# SCH_W-F-FC-HX2X_BASE.net
KiCad netlist of a schematic drawn in Altium Designer
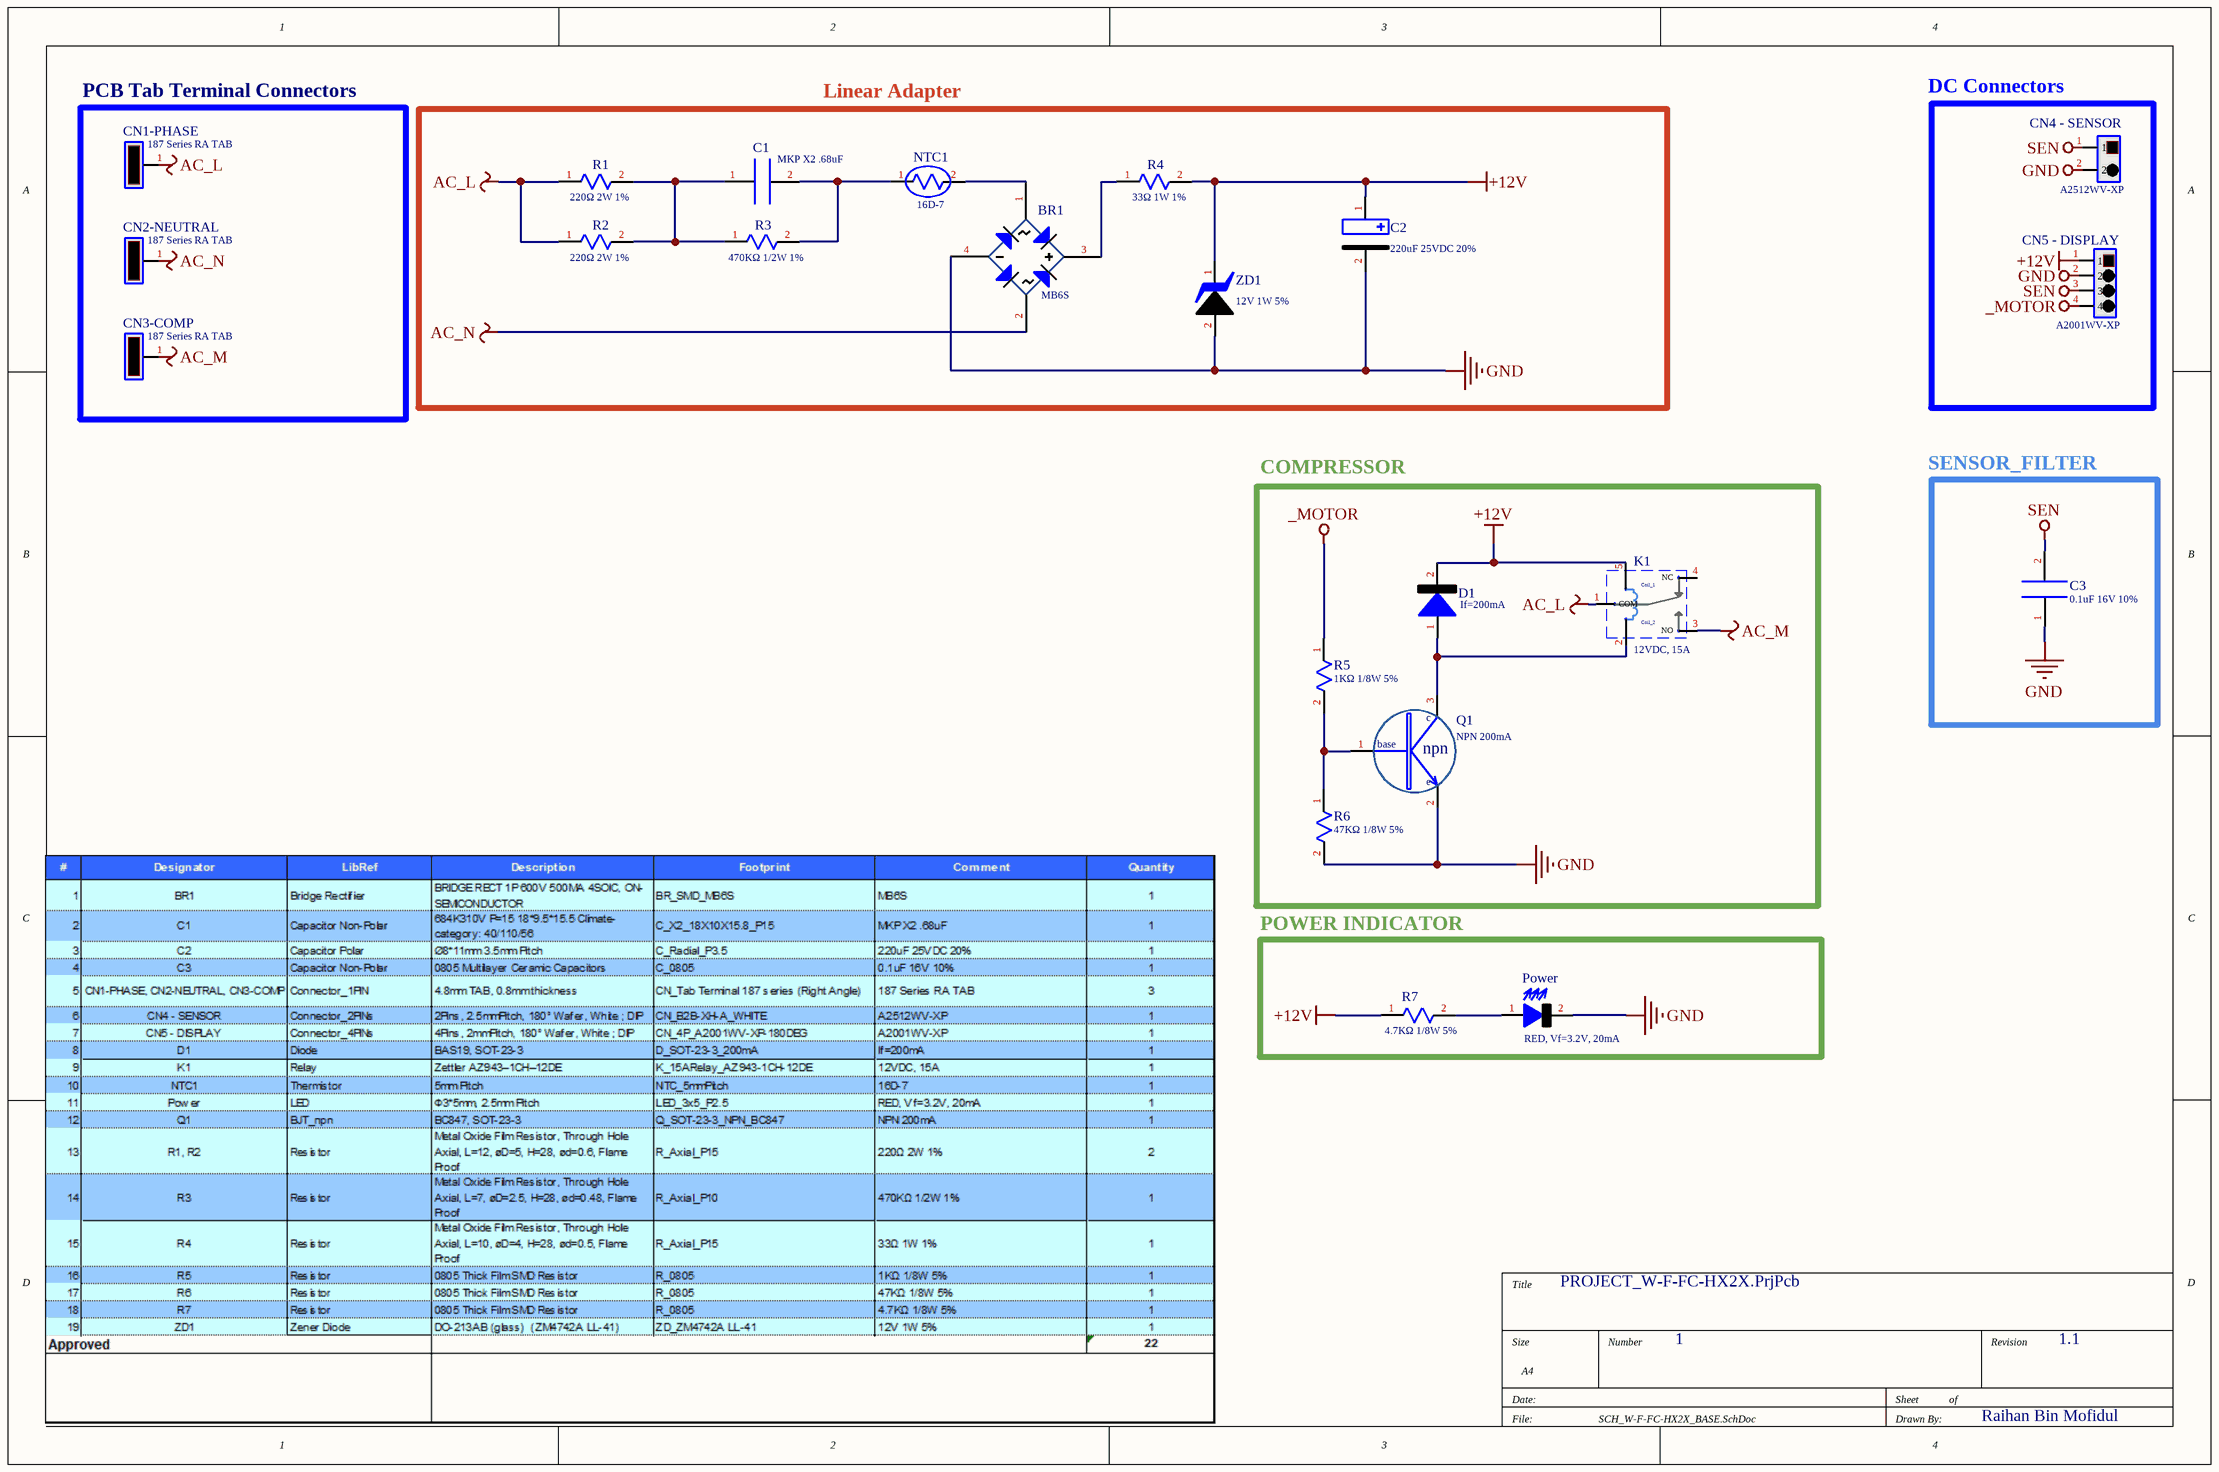
[diagram p0: SCH_W-F-FC-HX2X_BASE.SchDoc]

(export (version "E")
  (design (tool "Eeschema 10.0.6"))
  (components
    (comp (ref "BR1")
      (value "MB6S")
      (footprint "BR_SMD_MB6S")
      (description "BRIDGE RECT 1P 600V 500MA 4SOIC, ON-SEMICONDUCTOR")
      (libsource (lib "RBM_SCH-LIB_02-SEP-19") (part "Bridge Rectifier"))
    )
    (comp (ref "C1")
      (value "MKP X2 .68uF")
      (footprint "C_X2_18X10X15.8_P15")
      (description "684K310V P=15 18*9.5*15.5 Climate-category: 40/110/56")
      (libsource (lib "RBM_SCH-LIB_02-SEP-19") (part "Capacitor Non-Polar"))
    )
    (comp (ref "C2")
      (value "220uF 25VDC 20%")
      (footprint "C_Radial_P3.5")
      (description "Ø8*11mm 3.5mm Pitch")
      (libsource (lib "RBM_SCH-LIB_02-SEP-19") (part "Capacitor Polar"))
    )
    (comp (ref "C3")
      (value "0.1uF 16V 10%")
      (footprint "C_0805")
      (description "0805 Multilayer Ceramic Capacitors")
      (libsource (lib "RBM_SCH-Lib_16-Apr-19") (part "Capacitor Non-Polar"))
    )
    (comp (ref "CN1-PHASE")
      (value "187 Series RA TAB")
      (footprint "CN_Tab Terminal 187 series (Right Angle)")
      (description "4.8mm TAB, 0.8mm thickness")
      (libsource (lib "RBM_SCH-LIB_02-SEP-19") (part "Connector_1PIN"))
    )
    (comp (ref "CN2-NEUTRAL")
      (value "187 Series RA TAB")
      (footprint "CN_Tab Terminal 187 series (Right Angle)")
      (description "4.8mm TAB, 0.8mm thickness")
      (libsource (lib "RBM_SCH-LIB_02-SEP-19") (part "Connector_1PIN"))
    )
    (comp (ref "CN3-COMP")
      (value "187 Series RA TAB")
      (footprint "CN_Tab Terminal 187 series (Right Angle)")
      (description "4.8mm TAB, 0.8mm thickness")
      (libsource (lib "RBM_SCH-LIB_02-SEP-19") (part "Connector_1PIN"))
    )
    (comp (ref "CN4 - SENSOR")
      (value "A2512WV-XP")
      (footprint "CN_B2B-XH-A_WHITE")
      (description "2Pins, 2.5mmPitch, 180° Wafer, White ; DIP")
      (libsource (lib "RBM_SCH-Lib_16-Apr-19") (part "Connector_2PINs"))
    )
    (comp (ref "CN5 - DISPLAY")
      (value "A2001WV-XP")
      (footprint "CN_4P_A2001WV-XP-180DEG")
      (description "4Pins, 2mmPitch, 180° Wafer, White ; DIP")
      (libsource (lib "RBM_SCH-LIB_02-SEP-19") (part "Connector_4PINs"))
    )
    (comp (ref "D1")
      (value "If=200mA")
      (footprint "D_SOT-23-3_200mA")
      (description "BAS19, SOT-23-3")
      (libsource (lib "RBM_SCH-LIB_02-SEP-19") (part "Diode"))
    )
    (comp (ref "K1")
      (value "12VDC, 15A")
      (footprint "K_15ARelay_AZ943-1CH-12DE")
      (description "Zettler AZ943–1CH–12DE")
      (libsource (lib "RBM_SCH-Lib_16-Apr-19") (part "Relay"))
    )
    (comp (ref "NTC1")
      (value "16D-7")
      (footprint "NTC_5mmPitch")
      (description "5mm Pitch")
      (libsource (lib "RBM_SCH-LIB_02-SEP-19") (part "Thermistor"))
    )
    (comp (ref "Power")
      (value "RED, Vf=3.2V, 20mA")
      (footprint "LED_3x5_P2.5")
      (description "Φ3*5mm, 2.5mm Pitch")
      (libsource (lib "RBM_SCH-LIB_02-SEP-19") (part "LED"))
    )
    (comp (ref "Q1")
      (value "NPN 200mA")
      (footprint "Q_SOT-23-3_NPN_BC847")
      (description "BC847, SOT-23-3")
      (libsource (lib "RBM_SCH-Lib_16-Apr-19") (part "BJT_npn"))
    )
    (comp (ref "R1")
      (value "220Ω 2W 1%")
      (footprint "R_Axial_P15")
      (description "Metal Oxide Film Resistor, Through Hole Axial, L=12, øD=5, H=28, ød=0.6, Flame Proof")
      (libsource (lib "RBM_SCH-LIB_02-SEP-19") (part "Resistor"))
    )
    (comp (ref "R2")
      (value "220Ω 2W 1%")
      (footprint "R_Axial_P15")
      (description "Metal Oxide Film Resistor, Through Hole Axial, L=12, øD=5, H=28, ød=0.6, Flame Proof")
      (libsource (lib "RBM_SCH-LIB_02-SEP-19") (part "Resistor"))
    )
    (comp (ref "R3")
      (value "470KΩ 1/2W 1%")
      (footprint "R_Axial_P10")
      (description "Metal Oxide Film Resistor, Through Hole Axial, L=7, øD=2.5, H=28, ød=0.48, Flame Proof")
      (libsource (lib "RBM_SCH-LIB_02-SEP-19") (part "Resistor"))
    )
    (comp (ref "R4")
      (value "33Ω 1W 1%")
      (footprint "R_Axial_P15")
      (description "Metal Oxide Film Resistor, Through Hole Axial, L=10, øD=4, H=28, ød=0.5, Flame Proof")
      (libsource (lib "RBM_SCH-LIB_02-SEP-19") (part "Resistor"))
    )
    (comp (ref "R5")
      (value "1KΩ 1/8W 5%")
      (footprint "R_0805")
      (description "0805 Thick Film SMD Resistor")
      (libsource (lib "RBM_SCH-Lib_16-Apr-19") (part "Resistor"))
    )
    (comp (ref "R6")
      (value "47KΩ 1/8W 5%")
      (footprint "R_0805")
      (description "0805 Thick Film SMD Resistor")
      (libsource (lib "RBM_SCH-Lib_16-Apr-19") (part "Resistor"))
    )
    (comp (ref "R7")
      (value "4.7KΩ 1/8W 5%")
      (footprint "R_0805")
      (description "0805 Thick Film SMD Resistor")
      (libsource (lib "RBM_SCH-Lib_16-Apr-19") (part "Resistor"))
    )
    (comp (ref "ZD1")
      (value "12V 1W 5%")
      (footprint "ZD_ZM4742A LL-41")
      (description "DO-213AB (glass)  (ZM4742A LL-41)")
      (libsource (lib "RBM_SCH-LIB_02-SEP-19") (part "Zener Diode"))
    )
  )
  (nets
    (net (code "1") (name "+12V") (class "Default")
      (node (ref "C2") (pin "1") (pinfunction "vdd_1") (pintype "passive"))
      (node (ref "CN5 - DISPLAY") (pin "1") (pinfunction "1_1") (pintype "passive"))
      (node (ref "D1") (pin "2") (pinfunction "vss_2") (pintype "passive"))
      (node (ref "K1") (pin "5") (pinfunction "COIL1_5") (pintype "passive"))
      (node (ref "R4") (pin "2") (pinfunction "2_2") (pintype "passive"))
      (node (ref "R7") (pin "1") (pinfunction "1_1") (pintype "passive"))
      (node (ref "ZD1") (pin "1") (pinfunction "VCC_1") (pintype "passive"))
    )
    (net (code "2") (name "AC_L") (class "Default")
      (node (ref "CN1-PHASE") (pin "1") (pinfunction "1_1") (pintype "passive"))
      (node (ref "K1") (pin "1") (pinfunction "COM_1") (pintype "passive"))
      (node (ref "R1") (pin "1") (pinfunction "1_1") (pintype "passive"))
      (node (ref "R2") (pin "1") (pinfunction "1_1") (pintype "passive"))
    )
    (net (code "3") (name "AC_M") (class "Default")
      (node (ref "CN3-COMP") (pin "1") (pinfunction "1_1") (pintype "passive"))
      (node (ref "K1") (pin "3") (pinfunction "NO_3") (pintype "passive"))
    )
    (net (code "4") (name "AC_N") (class "Default")
      (node (ref "BR1") (pin "2") (pinfunction "AC_2") (pintype "passive"))
      (node (ref "CN2-NEUTRAL") (pin "1") (pinfunction "1_1") (pintype "passive"))
    )
    (net (code "5") (name "GND") (class "Default")
      (node (ref "BR1") (pin "4") (pinfunction "vss_4") (pintype "passive"))
      (node (ref "C2") (pin "2") (pinfunction "vss_2") (pintype "passive"))
      (node (ref "C3") (pin "1") (pinfunction "1_1") (pintype "passive"))
      (node (ref "CN4 - SENSOR") (pin "2") (pinfunction "2_2") (pintype "passive"))
      (node (ref "CN5 - DISPLAY") (pin "2") (pinfunction "2_2") (pintype "passive"))
      (node (ref "Power") (pin "2") (pinfunction "vss_2") (pintype "passive"))
      (node (ref "Q1") (pin "2") (pinfunction "Emitter_2") (pintype "passive"))
      (node (ref "R6") (pin "2") (pinfunction "2_2") (pintype "passive"))
      (node (ref "ZD1") (pin "2") (pinfunction "GND_2") (pintype "passive"))
    )
    (net (code "6") (name "Net-(BR1-AC-Pad1)") (class "Default")
      (node (ref "BR1") (pin "1") (pinfunction "AC_1") (pintype "passive"))
      (node (ref "NTC1") (pin "2") (pinfunction "2_2") (pintype "passive"))
    )
    (net (code "7") (name "Net-(BR1-VCC)") (class "Default")
      (node (ref "BR1") (pin "3") (pinfunction "VCC_3") (pintype "passive"))
      (node (ref "R4") (pin "1") (pinfunction "1_1") (pintype "passive"))
    )
    (net (code "8") (name "Net-(C1-Pad1)") (class "Default")
      (node (ref "C1") (pin "1") (pinfunction "1_1") (pintype "passive"))
      (node (ref "R1") (pin "2") (pinfunction "2_2") (pintype "passive"))
      (node (ref "R2") (pin "2") (pinfunction "2_2") (pintype "passive"))
      (node (ref "R3") (pin "1") (pinfunction "1_1") (pintype "passive"))
    )
    (net (code "9") (name "Net-(C1-Pad2)") (class "Default")
      (node (ref "C1") (pin "2") (pinfunction "2_2") (pintype "passive"))
      (node (ref "NTC1") (pin "1") (pinfunction "1_1") (pintype "passive"))
      (node (ref "R3") (pin "2") (pinfunction "2_2") (pintype "passive"))
    )
    (net (code "10") (name "Net-(D1-vdd)") (class "Default")
      (node (ref "D1") (pin "1") (pinfunction "vdd_1") (pintype "passive"))
      (node (ref "K1") (pin "2") (pinfunction "COIL2_2") (pintype "passive"))
      (node (ref "Q1") (pin "3") (pinfunction "Collector_3") (pintype "passive"))
    )
    (net (code "11") (name "Net-(Power-vdd)") (class "Default")
      (node (ref "Power") (pin "1") (pinfunction "vdd_1") (pintype "passive"))
      (node (ref "R7") (pin "2") (pinfunction "2_2") (pintype "passive"))
    )
    (net (code "12") (name "Net-(Q1-Base)") (class "Default")
      (node (ref "Q1") (pin "1") (pinfunction "Base_1") (pintype "passive"))
      (node (ref "R5") (pin "2") (pinfunction "2_2") (pintype "passive"))
      (node (ref "R6") (pin "1") (pinfunction "1_1") (pintype "passive"))
    )
    (net (code "13") (name "SEN") (class "Default")
      (node (ref "C3") (pin "2") (pinfunction "2_2") (pintype "passive"))
      (node (ref "CN4 - SENSOR") (pin "1") (pinfunction "1_1") (pintype "passive"))
      (node (ref "CN5 - DISPLAY") (pin "3") (pinfunction "3_3") (pintype "passive"))
    )
    (net (code "14") (name "_MOTOR") (class "Default")
      (node (ref "CN5 - DISPLAY") (pin "4") (pinfunction "4_4") (pintype "passive"))
      (node (ref "R5") (pin "1") (pinfunction "1_1") (pintype "passive"))
    )
    (net (code "15") (name "unconnected-(K1-NC-Pad4)") (class "Default")
      (node (ref "K1") (pin "4") (pinfunction "NC_4") (pintype "passive"))
    )
  )
)
